# FMC_connector.net
KiCad netlist of a schematic drawn in Altium Designer
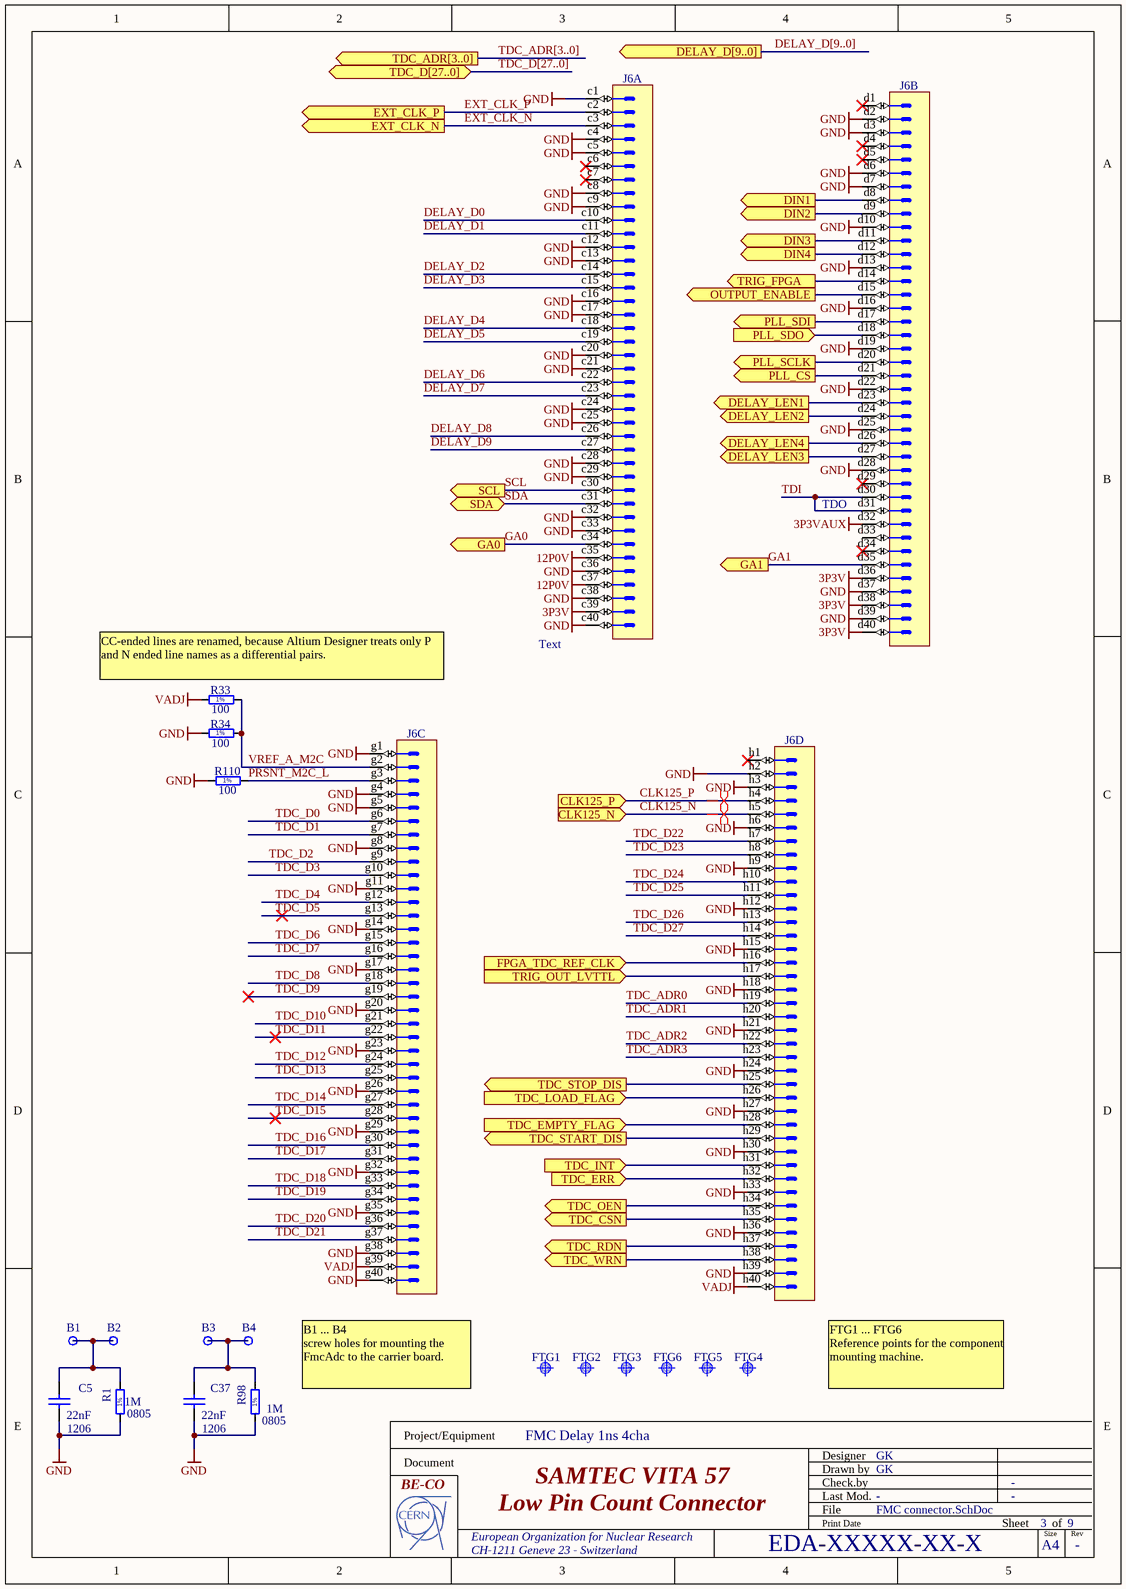
[diagram p0: FMC connector.SchDoc]

(export (version "E")
  (design (tool "Eeschema 10.0.6"))
  (components
    (comp (ref "B1")
      (value "Plated Hole")
      (footprint "MTG300_600")
      (description "Single Terminal Socket")
      (fields (field (name "PART NUMBER") "PLATED_HOLE3.0_PAD6.0") (field (name "AUTHOR") "CERN DEM JLC"))
      (libsource (lib "Eletro-mechanical") (part "Single Terminal Socket"))
    )
    (comp (ref "B2")
      (value "Plated Hole")
      (footprint "MTG300_600")
      (description "Single Terminal Socket")
      (fields (field (name "PART NUMBER") "PLATED_HOLE3.0_PAD6.0") (field (name "AUTHOR") "CERN DEM JLC"))
      (libsource (lib "Eletro-mechanical") (part "Single Terminal Socket"))
    )
    (comp (ref "B3")
      (value "Plated Hole")
      (footprint "MTG300_600")
      (description "Single Terminal Socket")
      (fields (field (name "PART NUMBER") "PLATED_HOLE3.0_PAD6.0") (field (name "AUTHOR") "CERN DEM JLC"))
      (libsource (lib "Eletro-mechanical") (part "Single Terminal Socket"))
    )
    (comp (ref "B4")
      (value "Plated Hole")
      (footprint "MTG300_600")
      (description "Single Terminal Socket")
      (fields (field (name "PART NUMBER") "PLATED_HOLE3.0_PAD6.0") (field (name "AUTHOR") "CERN DEM JLC"))
      (libsource (lib "Eletro-mechanical") (part "Single Terminal Socket"))
    )
    (comp (ref "C5")
      (value "22nF")
      (footprint "CAPC3216X140N")
      (description "Non-polarised capacitor")
      (fields
        (field (name "PART NUMBER") "CC1206_22NF_200V_10%_X7R")
        (field (name "VOLTAGE") "200V")
        (field (name "CASE") "1206")
        (field (name "AUTHOR") "CERN DEM JLC")
      )
      (libsource (lib "Capacitors") (part "Capacitor - non polarized"))
    )
    (comp (ref "C37")
      (value "22nF")
      (footprint "CAPC3216X140N")
      (description "Non-polarised capacitor")
      (fields
        (field (name "PART NUMBER") "CC1206_22NF_200V_10%_X7R")
        (field (name "VOLTAGE") "200V")
        (field (name "CASE") "1206")
        (field (name "AUTHOR") "CERN DEM JLC")
      )
      (libsource (lib "Capacitors") (part "Capacitor - non polarized"))
    )
    (comp (ref "FTG1")
      (value "Use only in PCB")
      (footprint "FIDUCIAL_TOP_S100-200")
      (description "Fiducial Target")
      (fields (field (name "PART NUMBER") "FIDUCIAL_TARGET_S100-200") (field (name "AUTHOR") "CERN DEM JLC"))
      (libsource (lib "Eletro-mechanical") (part "Fiducial Target"))
    )
    (comp (ref "FTG2")
      (value "Use only in PCB")
      (footprint "FIDUCIAL_TOP_S100-200")
      (description "Fiducial Target")
      (fields (field (name "PART NUMBER") "FIDUCIAL_TARGET_S100-200") (field (name "AUTHOR") "CERN DEM JLC"))
      (libsource (lib "Eletro-mechanical") (part "Fiducial Target"))
    )
    (comp (ref "FTG3")
      (value "Use only in PCB")
      (footprint "FIDUCIAL_TOP_S100-200")
      (description "Fiducial Target")
      (fields (field (name "PART NUMBER") "FIDUCIAL_TARGET_S100-200") (field (name "AUTHOR") "CERN DEM JLC"))
      (libsource (lib "Eletro-mechanical") (part "Fiducial Target"))
    )
    (comp (ref "FTG4")
      (value "Use only in PCB")
      (footprint "FIDUCIAL_TOP_S100-200")
      (description "Fiducial Target")
      (fields (field (name "PART NUMBER") "FIDUCIAL_TARGET_S100-200") (field (name "AUTHOR") "CERN DEM JLC"))
      (libsource (lib "Eletro-mechanical") (part "Fiducial Target"))
    )
    (comp (ref "FTG5")
      (value "Use only in PCB")
      (footprint "FIDUCIAL_TOP_S100-200")
      (description "Fiducial Target")
      (fields (field (name "PART NUMBER") "FIDUCIAL_TARGET_S100-200") (field (name "AUTHOR") "CERN DEM JLC"))
      (libsource (lib "Eletro-mechanical") (part "Fiducial Target"))
    )
    (comp (ref "FTG6")
      (value "Use only in PCB")
      (footprint "FIDUCIAL_TOP_S100-200")
      (description "Fiducial Target")
      (fields (field (name "PART NUMBER") "FIDUCIAL_TARGET_S100-200") (field (name "AUTHOR") "CERN DEM JLC"))
      (libsource (lib "Eletro-mechanical") (part "Fiducial Target"))
    )
    (comp (ref "J6")
      (value "VITA 57")
      (footprint "SAMTEC_ASP-127797-01")
      (description "Connector VITA 57, 160 Male contacts in 4 row cdgh")
      (fields
        (field (name "PART NUMBER") "SAMTEC_ASP-127797-01")
        (field (name "MANUFACTURER") "SAMTEC")
        (field (name "AUTHOR") "CERN DEM JLC")
      )
      (libsource (lib "Connectors") (part "Connector VITA 57 160 Male (cdgh)"))
    )
    (comp (ref "R1")
      (value "1M")
      (footprint "RESC2012X60N")
      (description "Resistor - 1%")
      (fields
        (field (name "PART NUMBER") "R0805_1M_1%_0.125W_100PPM")
        (field (name "POWER") "0.125W")
        (field (name "CASE") "0805")
        (field (name "AUTHOR") "CERN DEM JLC")
      )
      (libsource (lib "Resistors") (part "Resistor - 1%"))
    )
    (comp (ref "R33")
      (value "100")
      (footprint "RESC1608X55N")
      (description "Resistor - 1%")
      (fields
        (field (name "PART NUMBER") "R0603_100R_1%_0.1W_100PPM")
        (field (name "POWER") "0.1W")
        (field (name "AUTHOR") "CERN DEM JLC")
      )
      (libsource (lib "Resistors") (part "Resistor - 1%"))
    )
    (comp (ref "R34")
      (value "100")
      (footprint "RESC1608X55N")
      (description "Resistor - 1%")
      (fields
        (field (name "PART NUMBER") "R0603_100R_1%_0.1W_100PPM")
        (field (name "POWER") "0.1W")
        (field (name "AUTHOR") "CERN DEM JLC")
      )
      (libsource (lib "Resistors") (part "Resistor - 1%"))
    )
    (comp (ref "R98")
      (value "1M")
      (footprint "RESC2012X60N")
      (description "Resistor - 1%")
      (fields
        (field (name "PART NUMBER") "R0805_1M_1%_0.125W_100PPM")
        (field (name "POWER") "0.125W")
        (field (name "CASE") "0805")
        (field (name "AUTHOR") "CERN DEM JLC")
      )
      (libsource (lib "Resistors") (part "Resistor - 1%"))
    )
    (comp (ref "R110")
      (value "100")
      (footprint "RESC1608X55N")
      (description "Resistor - 1%")
      (fields
        (field (name "PART NUMBER") "R0603_100R_1%_0.1W_100PPM")
        (field (name "POWER") "0.1W")
        (field (name "AUTHOR") "CERN DEM JLC")
      )
      (libsource (lib "Resistors") (part "Resistor - 1%"))
    )
  )
  (nets
    (net (code "1") (name "/CLK125_N") (class "Default")
      (node (ref "J6") (pin "h5") (pinfunction "h5_h5") (pintype "bidirectional"))
    )
    (net (code "2") (name "/CLK125_P") (class "Default")
      (node (ref "J6") (pin "h4") (pinfunction "h4_h4") (pintype "bidirectional"))
    )
    (net (code "3") (name "/DELAY_D0") (class "Default")
      (node (ref "J6") (pin "c10") (pinfunction "c10_c10") (pintype "bidirectional"))
    )
    (net (code "4") (name "/DELAY_D1") (class "Default")
      (node (ref "J6") (pin "c11") (pinfunction "c11_c11") (pintype "bidirectional"))
    )
    (net (code "5") (name "/DELAY_D2") (class "Default")
      (node (ref "J6") (pin "c14") (pinfunction "c14_c14") (pintype "bidirectional"))
    )
    (net (code "6") (name "/DELAY_D3") (class "Default")
      (node (ref "J6") (pin "c15") (pinfunction "c15_c15") (pintype "bidirectional"))
    )
    (net (code "7") (name "/DELAY_D4") (class "Default")
      (node (ref "J6") (pin "c18") (pinfunction "c18_c18") (pintype "bidirectional"))
    )
    (net (code "8") (name "/DELAY_D5") (class "Default")
      (node (ref "J6") (pin "c19") (pinfunction "c19_c19") (pintype "bidirectional"))
    )
    (net (code "9") (name "/DELAY_D6") (class "Default")
      (node (ref "J6") (pin "c22") (pinfunction "c22_c22") (pintype "bidirectional"))
    )
    (net (code "10") (name "/DELAY_D7") (class "Default")
      (node (ref "J6") (pin "c23") (pinfunction "c23_c23") (pintype "bidirectional"))
    )
    (net (code "11") (name "/DELAY_D8") (class "Default")
      (node (ref "J6") (pin "c26") (pinfunction "c26_c26") (pintype "bidirectional"))
    )
    (net (code "12") (name "/DELAY_D9") (class "Default")
      (node (ref "J6") (pin "c27") (pinfunction "c27_c27") (pintype "bidirectional"))
    )
    (net (code "14") (name "/DELAY_LEN1") (class "Default")
      (node (ref "J6") (pin "d23") (pinfunction "d23_d23") (pintype "bidirectional"))
    )
    (net (code "15") (name "/DELAY_LEN2") (class "Default")
      (node (ref "J6") (pin "d24") (pinfunction "d24_d24") (pintype "bidirectional"))
    )
    (net (code "16") (name "/DELAY_LEN3") (class "Default")
      (node (ref "J6") (pin "d27") (pinfunction "d27_d27") (pintype "bidirectional"))
    )
    (net (code "17") (name "/DELAY_LEN4") (class "Default")
      (node (ref "J6") (pin "d26") (pinfunction "d26_d26") (pintype "bidirectional"))
    )
    (net (code "18") (name "/DIN1") (class "Default")
      (node (ref "J6") (pin "d8") (pinfunction "d8_d8") (pintype "bidirectional"))
    )
    (net (code "19") (name "/DIN2") (class "Default")
      (node (ref "J6") (pin "d9") (pinfunction "d9_d9") (pintype "bidirectional"))
    )
    (net (code "20") (name "/DIN3") (class "Default")
      (node (ref "J6") (pin "d11") (pinfunction "d11_d11") (pintype "bidirectional"))
    )
    (net (code "21") (name "/DIN4") (class "Default")
      (node (ref "J6") (pin "d12") (pinfunction "d12_d12") (pintype "bidirectional"))
    )
    (net (code "22") (name "/EXT_CLK_N") (class "Default")
      (node (ref "J6") (pin "c3") (pinfunction "c3_c3") (pintype "bidirectional"))
    )
    (net (code "23") (name "/EXT_CLK_P") (class "Default")
      (node (ref "J6") (pin "c2") (pinfunction "c2_c2") (pintype "bidirectional"))
    )
    (net (code "24") (name "/FPGA_TDC_REF_CLK") (class "Default")
      (node (ref "J6") (pin "h16") (pinfunction "h16_h16") (pintype "bidirectional"))
    )
    (net (code "25") (name "/GA0") (class "Default")
      (node (ref "J6") (pin "c34") (pinfunction "c34_c34") (pintype "bidirectional"))
    )
    (net (code "26") (name "/GA1") (class "Default")
      (node (ref "J6") (pin "d35") (pinfunction "d35_d35") (pintype "bidirectional"))
    )
    (net (code "27") (name "/OUTPUT_ENABLE") (class "Default")
      (node (ref "J6") (pin "d15") (pinfunction "d15_d15") (pintype "bidirectional"))
    )
    (net (code "28") (name "/PLL_CS") (class "Default")
      (node (ref "J6") (pin "d21") (pinfunction "d21_d21") (pintype "bidirectional"))
    )
    (net (code "29") (name "/PLL_SCLK") (class "Default")
      (node (ref "J6") (pin "d20") (pinfunction "d20_d20") (pintype "bidirectional"))
    )
    (net (code "30") (name "/PLL_SDI") (class "Default")
      (node (ref "J6") (pin "d17") (pinfunction "d17_d17") (pintype "bidirectional"))
    )
    (net (code "31") (name "/PLL_SDO") (class "Default")
      (node (ref "J6") (pin "d18") (pinfunction "d18_d18") (pintype "bidirectional"))
    )
    (net (code "32") (name "/PRSNT_M2C_L") (class "Default")
      (node (ref "J6") (pin "g3") (pinfunction "g3_g3") (pintype "bidirectional"))
      (node (ref "R110") (pin "2") (pinfunction "2_2") (pintype "passive"))
    )
    (net (code "33") (name "/SCL") (class "Default")
      (node (ref "J6") (pin "c30") (pinfunction "c30_c30") (pintype "bidirectional"))
    )
    (net (code "34") (name "/SDA") (class "Default")
      (node (ref "J6") (pin "c31") (pinfunction "c31_c31") (pintype "bidirectional"))
    )
    (net (code "35") (name "/TDC_ADR0") (class "Default")
      (node (ref "J6") (pin "h19") (pinfunction "h19_h19") (pintype "bidirectional"))
    )
    (net (code "36") (name "/TDC_ADR1") (class "Default")
      (node (ref "J6") (pin "h20") (pinfunction "h20_h20") (pintype "bidirectional"))
    )
    (net (code "37") (name "/TDC_ADR2") (class "Default")
      (node (ref "J6") (pin "h22") (pinfunction "h22_h22") (pintype "bidirectional"))
    )
    (net (code "38") (name "/TDC_ADR3") (class "Default")
      (node (ref "J6") (pin "h23") (pinfunction "h23_h23") (pintype "bidirectional"))
    )
    (net (code "40") (name "/TDC_CSN") (class "Default")
      (node (ref "J6") (pin "h35") (pinfunction "h35_h35") (pintype "bidirectional"))
    )
    (net (code "41") (name "/TDC_D0") (class "Default")
      (node (ref "J6") (pin "g6") (pinfunction "g6_g6") (pintype "bidirectional"))
    )
    (net (code "42") (name "/TDC_D1") (class "Default")
      (node (ref "J6") (pin "g7") (pinfunction "g7_g7") (pintype "bidirectional"))
    )
    (net (code "43") (name "/TDC_D2") (class "Default")
      (node (ref "J6") (pin "g9") (pinfunction "g9_g9") (pintype "bidirectional"))
    )
    (net (code "44") (name "/TDC_D3") (class "Default")
      (node (ref "J6") (pin "g10") (pinfunction "g10_g10") (pintype "bidirectional"))
    )
    (net (code "45") (name "/TDC_D4") (class "Default")
      (node (ref "J6") (pin "g12") (pinfunction "g12_g12") (pintype "bidirectional"))
    )
    (net (code "46") (name "/TDC_D5") (class "Default")
      (node (ref "J6") (pin "g13") (pinfunction "g13_g13") (pintype "bidirectional"))
    )
    (net (code "47") (name "/TDC_D6") (class "Default")
      (node (ref "J6") (pin "g15") (pinfunction "g15_g15") (pintype "bidirectional"))
    )
    (net (code "48") (name "/TDC_D7") (class "Default")
      (node (ref "J6") (pin "g16") (pinfunction "g16_g16") (pintype "bidirectional"))
    )
    (net (code "49") (name "/TDC_D8") (class "Default")
      (node (ref "J6") (pin "g18") (pinfunction "g18_g18") (pintype "bidirectional"))
    )
    (net (code "50") (name "/TDC_D9") (class "Default")
      (node (ref "J6") (pin "g19") (pinfunction "g19_g19") (pintype "bidirectional+no_connect"))
    )
    (net (code "51") (name "/TDC_D10") (class "Default")
      (node (ref "J6") (pin "g21") (pinfunction "g21_g21") (pintype "bidirectional"))
    )
    (net (code "53") (name "/TDC_D11") (class "Default")
      (node (ref "J6") (pin "g22") (pinfunction "g22_g22") (pintype "bidirectional"))
    )
    (net (code "54") (name "/TDC_D12") (class "Default")
      (node (ref "J6") (pin "g24") (pinfunction "g24_g24") (pintype "bidirectional"))
    )
    (net (code "55") (name "/TDC_D13") (class "Default")
      (node (ref "J6") (pin "g25") (pinfunction "g25_g25") (pintype "bidirectional"))
    )
    (net (code "57") (name "/TDC_D14") (class "Default")
      (node (ref "J6") (pin "g27") (pinfunction "g27_g27") (pintype "bidirectional"))
    )
    (net (code "58") (name "/TDC_D15") (class "Default")
      (node (ref "J6") (pin "g28") (pinfunction "g28_g28") (pintype "bidirectional"))
    )
    (net (code "59") (name "/TDC_D16") (class "Default")
      (node (ref "J6") (pin "g30") (pinfunction "g30_g30") (pintype "bidirectional"))
    )
    (net (code "60") (name "/TDC_D17") (class "Default")
      (node (ref "J6") (pin "g31") (pinfunction "g31_g31") (pintype "bidirectional"))
    )
    (net (code "61") (name "/TDC_D18") (class "Default")
      (node (ref "J6") (pin "g33") (pinfunction "g33_g33") (pintype "bidirectional"))
    )
    (net (code "62") (name "/TDC_D19") (class "Default")
      (node (ref "J6") (pin "g34") (pinfunction "g34_g34") (pintype "bidirectional"))
    )
    (net (code "63") (name "/TDC_D20") (class "Default")
      (node (ref "J6") (pin "g36") (pinfunction "g36_g36") (pintype "bidirectional"))
    )
    (net (code "64") (name "/TDC_D21") (class "Default")
      (node (ref "J6") (pin "g37") (pinfunction "g37_g37") (pintype "bidirectional"))
    )
    (net (code "65") (name "/TDC_D22") (class "Default")
      (node (ref "J6") (pin "h7") (pinfunction "h7_h7") (pintype "bidirectional"))
    )
    (net (code "66") (name "/TDC_D23") (class "Default")
      (node (ref "J6") (pin "h8") (pinfunction "h8_h8") (pintype "bidirectional"))
    )
    (net (code "67") (name "/TDC_D24") (class "Default")
      (node (ref "J6") (pin "h10") (pinfunction "h10_h10") (pintype "bidirectional"))
    )
    (net (code "68") (name "/TDC_D25") (class "Default")
      (node (ref "J6") (pin "h11") (pinfunction "h11_h11") (pintype "bidirectional"))
    )
    (net (code "70") (name "/TDC_D26") (class "Default")
      (node (ref "J6") (pin "h13") (pinfunction "h13_h13") (pintype "bidirectional"))
    )
    (net (code "71") (name "/TDC_D27") (class "Default")
      (node (ref "J6") (pin "h14") (pinfunction "h14_h14") (pintype "bidirectional"))
    )
    (net (code "72") (name "/TDC_EMPTY_FLAG") (class "Default")
      (node (ref "J6") (pin "h28") (pinfunction "h28_h28") (pintype "bidirectional"))
    )
    (net (code "73") (name "/TDC_ERR") (class "Default")
      (node (ref "J6") (pin "h32") (pinfunction "h32_h32") (pintype "bidirectional"))
    )
    (net (code "74") (name "/TDC_INT") (class "Default")
      (node (ref "J6") (pin "h31") (pinfunction "h31_h31") (pintype "bidirectional"))
    )
    (net (code "75") (name "/TDC_LOAD_FLAG") (class "Default")
      (node (ref "J6") (pin "h26") (pinfunction "h26_h26") (pintype "bidirectional"))
    )
    (net (code "76") (name "/TDC_OEN") (class "Default")
      (node (ref "J6") (pin "h34") (pinfunction "h34_h34") (pintype "bidirectional"))
    )
    (net (code "77") (name "/TDC_RDN") (class "Default")
      (node (ref "J6") (pin "h37") (pinfunction "h37_h37") (pintype "bidirectional"))
    )
    (net (code "78") (name "/TDC_START_DIS") (class "Default")
      (node (ref "J6") (pin "h29") (pinfunction "h29_h29") (pintype "bidirectional"))
    )
    (net (code "79") (name "/TDC_STOP_DIS") (class "Default")
      (node (ref "J6") (pin "h25") (pinfunction "h25_h25") (pintype "bidirectional"))
    )
    (net (code "80") (name "/TDC_WRN") (class "Default")
      (node (ref "J6") (pin "h38") (pinfunction "h38_h38") (pintype "bidirectional"))
    )
    (net (code "81") (name "/TDI") (class "Default")
      (node (ref "J6") (pin "d30") (pinfunction "d30_d30") (pintype "bidirectional"))
      (node (ref "J6") (pin "d31") (pinfunction "d31_d31") (pintype "bidirectional"))
    )
    (net (code "82") (name "/TRIG_FPGA") (class "Default")
      (node (ref "J6") (pin "d14") (pinfunction "d14_d14") (pintype "bidirectional"))
    )
    (net (code "83") (name "/TRIG_OUT_LVTTL") (class "Default")
      (node (ref "J6") (pin "h17") (pinfunction "h17_h17") (pintype "bidirectional"))
    )
    (net (code "84") (name "/VREF_A_M2C") (class "Default")
      (node (ref "J6") (pin "g2") (pinfunction "g2_g2") (pintype "bidirectional"))
      (node (ref "R33") (pin "2") (pinfunction "2_2") (pintype "passive"))
      (node (ref "R34") (pin "2") (pinfunction "2_2") (pintype "passive"))
    )
    (net (code "85") (name "3P3V") (class "Default")
      (node (ref "J6") (pin "c39") (pinfunction "c39_c39") (pintype "bidirectional"))
      (node (ref "J6") (pin "d36") (pinfunction "d36_d36") (pintype "bidirectional"))
      (node (ref "J6") (pin "d38") (pinfunction "d38_d38") (pintype "bidirectional"))
      (node (ref "J6") (pin "d40") (pinfunction "d40_d40") (pintype "bidirectional"))
    )
    (net (code "86") (name "3P3VAUX") (class "Default")
      (node (ref "J6") (pin "d32") (pinfunction "d32_d32") (pintype "bidirectional"))
    )
    (net (code "87") (name "12P0V") (class "Default")
      (node (ref "J6") (pin "c35") (pinfunction "c35_c35") (pintype "bidirectional"))
      (node (ref "J6") (pin "c37") (pinfunction "c37_c37") (pintype "bidirectional"))
    )
    (net (code "88") (name "GND") (class "Default")
      (node (ref "C37") (pin "2") (pinfunction "2_2") (pintype "passive"))
      (node (ref "C5") (pin "2") (pinfunction "2_2") (pintype "passive"))
      (node (ref "J6") (pin "c1") (pinfunction "c1_c1") (pintype "bidirectional"))
      (node (ref "J6") (pin "c12") (pinfunction "c12_c12") (pintype "bidirectional"))
      (node (ref "J6") (pin "c13") (pinfunction "c13_c13") (pintype "bidirectional"))
      (node (ref "J6") (pin "c16") (pinfunction "c16_c16") (pintype "bidirectional"))
      (node (ref "J6") (pin "c17") (pinfunction "c17_c17") (pintype "bidirectional"))
      (node (ref "J6") (pin "c20") (pinfunction "c20_c20") (pintype "bidirectional"))
      (node (ref "J6") (pin "c21") (pinfunction "c21_c21") (pintype "bidirectional"))
      (node (ref "J6") (pin "c24") (pinfunction "c24_c24") (pintype "bidirectional"))
      (node (ref "J6") (pin "c25") (pinfunction "c25_c25") (pintype "bidirectional"))
      (node (ref "J6") (pin "c28") (pinfunction "c28_c28") (pintype "bidirectional"))
      (node (ref "J6") (pin "c29") (pinfunction "c29_c29") (pintype "bidirectional"))
      (node (ref "J6") (pin "c32") (pinfunction "c32_c32") (pintype "bidirectional"))
      (node (ref "J6") (pin "c33") (pinfunction "c33_c33") (pintype "bidirectional"))
      (node (ref "J6") (pin "c36") (pinfunction "c36_c36") (pintype "bidirectional"))
      (node (ref "J6") (pin "c38") (pinfunction "c38_c38") (pintype "bidirectional"))
      (node (ref "J6") (pin "c4") (pinfunction "c4_c4") (pintype "bidirectional"))
      (node (ref "J6") (pin "c40") (pinfunction "c40_c40") (pintype "bidirectional"))
      (node (ref "J6") (pin "c5") (pinfunction "c5_c5") (pintype "bidirectional"))
      (node (ref "J6") (pin "c8") (pinfunction "c8_c8") (pintype "bidirectional"))
      (node (ref "J6") (pin "c9") (pinfunction "c9_c9") (pintype "bidirectional"))
      (node (ref "J6") (pin "d10") (pinfunction "d10_d10") (pintype "bidirectional"))
      (node (ref "J6") (pin "d13") (pinfunction "d13_d13") (pintype "bidirectional"))
      (node (ref "J6") (pin "d16") (pinfunction "d16_d16") (pintype "bidirectional"))
      (node (ref "J6") (pin "d19") (pinfunction "d19_d19") (pintype "bidirectional"))
      (node (ref "J6") (pin "d2") (pinfunction "d2_d2") (pintype "bidirectional"))
      (node (ref "J6") (pin "d22") (pinfunction "d22_d22") (pintype "bidirectional"))
      (node (ref "J6") (pin "d25") (pinfunction "d25_d25") (pintype "bidirectional"))
      (node (ref "J6") (pin "d28") (pinfunction "d28_d28") (pintype "bidirectional"))
      (node (ref "J6") (pin "d3") (pinfunction "d3_d3") (pintype "bidirectional"))
      (node (ref "J6") (pin "d37") (pinfunction "d37_d37") (pintype "bidirectional"))
      (node (ref "J6") (pin "d39") (pinfunction "d39_d39") (pintype "bidirectional"))
      (node (ref "J6") (pin "d6") (pinfunction "d6_d6") (pintype "bidirectional"))
      (node (ref "J6") (pin "d7") (pinfunction "d7_d7") (pintype "bidirectional"))
      (node (ref "J6") (pin "g1") (pinfunction "g1_g1") (pintype "bidirectional"))
      (node (ref "J6") (pin "g11") (pinfunction "g11_g11") (pintype "bidirectional"))
      (node (ref "J6") (pin "g14") (pinfunction "g14_g14") (pintype "bidirectional"))
      (node (ref "J6") (pin "g17") (pinfunction "g17_g17") (pintype "bidirectional"))
      (node (ref "J6") (pin "g20") (pinfunction "g20_g20") (pintype "bidirectional"))
      (node (ref "J6") (pin "g23") (pinfunction "g23_g23") (pintype "bidirectional"))
      (node (ref "J6") (pin "g26") (pinfunction "g26_g26") (pintype "bidirectional"))
      (node (ref "J6") (pin "g29") (pinfunction "g29_g29") (pintype "bidirectional"))
      (node (ref "J6") (pin "g32") (pinfunction "g32_g32") (pintype "bidirectional"))
      (node (ref "J6") (pin "g35") (pinfunction "g35_g35") (pintype "bidirectional"))
      (node (ref "J6") (pin "g38") (pinfunction "g38_g38") (pintype "bidirectional"))
      (node (ref "J6") (pin "g4") (pinfunction "g4_g4") (pintype "bidirectional"))
      (node (ref "J6") (pin "g40") (pinfunction "g40_g40") (pintype "bidirectional"))
      (node (ref "J6") (pin "g5") (pinfunction "g5_g5") (pintype "bidirectional"))
      (node (ref "J6") (pin "g8") (pinfunction "g8_g8") (pintype "bidirectional"))
      (node (ref "J6") (pin "h12") (pinfunction "h12_h12") (pintype "bidirectional"))
      (node (ref "J6") (pin "h15") (pinfunction "h15_h15") (pintype "bidirectional"))
      (node (ref "J6") (pin "h18") (pinfunction "h18_h18") (pintype "bidirectional"))
      (node (ref "J6") (pin "h2") (pinfunction "h2_h2") (pintype "bidirectional"))
      (node (ref "J6") (pin "h21") (pinfunction "h21_h21") (pintype "bidirectional"))
      (node (ref "J6") (pin "h24") (pinfunction "h24_h24") (pintype "bidirectional"))
      (node (ref "J6") (pin "h27") (pinfunction "h27_h27") (pintype "bidirectional"))
      (node (ref "J6") (pin "h3") (pinfunction "h3_h3") (pintype "bidirectional"))
      (node (ref "J6") (pin "h30") (pinfunction "h30_h30") (pintype "bidirectional"))
      (node (ref "J6") (pin "h33") (pinfunction "h33_h33") (pintype "bidirectional"))
      (node (ref "J6") (pin "h36") (pinfunction "h36_h36") (pintype "bidirectional"))
      (node (ref "J6") (pin "h39") (pinfunction "h39_h39") (pintype "bidirectional"))
      (node (ref "J6") (pin "h6") (pinfunction "h6_h6") (pintype "bidirectional"))
      (node (ref "J6") (pin "h9") (pinfunction "h9_h9") (pintype "bidirectional"))
      (node (ref "R1") (pin "1") (pinfunction "1_1") (pintype "passive"))
      (node (ref "R110") (pin "1") (pinfunction "1_1") (pintype "passive"))
      (node (ref "R34") (pin "1") (pinfunction "1_1") (pintype "passive"))
      (node (ref "R98") (pin "1") (pinfunction "1_1") (pintype "passive"))
    )
    (net (code "89") (name "Net-(B1-Pad1)") (class "Default")
      (node (ref "B1") (pin "1") (pinfunction "1_1") (pintype "bidirectional"))
      (node (ref "B2") (pin "1") (pinfunction "1_1") (pintype "bidirectional"))
      (node (ref "C5") (pin "1") (pinfunction "1_1") (pintype "passive"))
      (node (ref "R1") (pin "2") (pinfunction "2_2") (pintype "passive"))
    )
    (net (code "90") (name "Net-(B3-Pad1)") (class "Default")
      (node (ref "B3") (pin "1") (pinfunction "1_1") (pintype "bidirectional"))
      (node (ref "B4") (pin "1") (pinfunction "1_1") (pintype "bidirectional"))
      (node (ref "C37") (pin "1") (pinfunction "1_1") (pintype "passive"))
      (node (ref "R98") (pin "2") (pinfunction "2_2") (pintype "passive"))
    )
    (net (code "91") (name "VADJ") (class "Default")
      (node (ref "J6") (pin "g39") (pinfunction "g39_g39") (pintype "bidirectional"))
      (node (ref "J6") (pin "h40") (pinfunction "h40_h40") (pintype "bidirectional"))
      (node (ref "R33") (pin "1") (pinfunction "1_1") (pintype "passive"))
    )
    (net (code "92") (name "unconnected-(J6-Padc6)") (class "Default")
      (node (ref "J6") (pin "c6") (pinfunction "c6_c6") (pintype "bidirectional+no_connect"))
    )
    (net (code "93") (name "unconnected-(J6-Padc7)") (class "Default")
      (node (ref "J6") (pin "c7") (pinfunction "c7_c7") (pintype "bidirectional+no_connect"))
    )
    (net (code "94") (name "unconnected-(J6-Padd1)") (class "Default")
      (node (ref "J6") (pin "d1") (pinfunction "d1_d1") (pintype "bidirectional+no_connect"))
    )
    (net (code "95") (name "unconnected-(J6-Padd4)") (class "Default")
      (node (ref "J6") (pin "d4") (pinfunction "d4_d4") (pintype "bidirectional+no_connect"))
    )
    (net (code "96") (name "unconnected-(J6-Padd5)") (class "Default")
      (node (ref "J6") (pin "d5") (pinfunction "d5_d5") (pintype "bidirectional+no_connect"))
    )
    (net (code "97") (name "unconnected-(J6-Padd29)") (class "Default")
      (node (ref "J6") (pin "d29") (pinfunction "d29_d29") (pintype "bidirectional+no_connect"))
    )
    (net (code "98") (name "unconnected-(J6-Padd33)") (class "Default")
      (node (ref "J6") (pin "d33") (pinfunction "d33_d33") (pintype "bidirectional"))
    )
    (net (code "99") (name "unconnected-(J6-Padd34)") (class "Default")
      (node (ref "J6") (pin "d34") (pinfunction "d34_d34") (pintype "bidirectional+no_connect"))
    )
    (net (code "100") (name "unconnected-(J6-Padh1)") (class "Default")
      (node (ref "J6") (pin "h1") (pinfunction "h1_h1") (pintype "bidirectional+no_connect"))
    )
  )
)
